# windsensor-esp12-v001.net
KiCad netlist of a schematic drawn in EAGLE
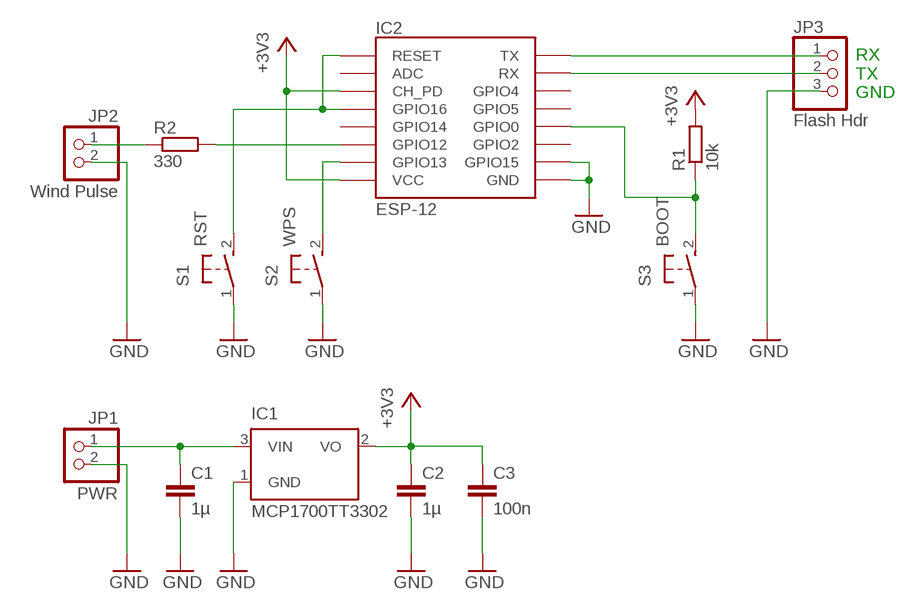
[diagram p0: schematic, sheet 1]

(export (version "E")
  (design (tool "Eeschema 10.0.6"))
  (components
    (comp (ref "C1")
      (value "1µ")
      (footprint "eagle-import:C0805")
      (libsource (lib "eagle-import") (part "C-EUC0805"))
    )
    (comp (ref "C2")
      (value "1µ")
      (footprint "eagle-import:C0805")
      (libsource (lib "eagle-import") (part "C-EUC0805"))
    )
    (comp (ref "C3")
      (value "100n")
      (footprint "eagle-import:C0805")
      (libsource (lib "eagle-import") (part "C-EUC0805"))
    )
    (comp (ref "IC1")
      (value "MCP1700TT3302")
      (footprint "eagle-import:SOT23")
      (libsource (lib "eagle-import") (part "MCP1700TT"))
    )
    (comp (ref "IC2")
      (value "ESP-12")
      (footprint "eagle-import:ESP-12")
      (libsource (lib "eagle-import") (part "ESP-12"))
    )
    (comp (ref "JP1")
      (value "PWR")
      (footprint "eagle-import:1X02")
      (libsource (lib "eagle-import") (part "PINHD-1X2"))
    )
    (comp (ref "JP2")
      (value "Wind Pulse")
      (footprint "eagle-import:1X02")
      (libsource (lib "eagle-import") (part "PINHD-1X2"))
    )
    (comp (ref "JP3")
      (value "Flash Hdr")
      (footprint "eagle-import:1X03")
      (libsource (lib "eagle-import") (part "PINHD-1X3"))
    )
    (comp (ref "R1")
      (value "10k")
      (footprint "eagle-import:R0805HS")
      (libsource (lib "eagle-import") (part "R-EU_R0805HS"))
    )
    (comp (ref "R2")
      (value "330")
      (footprint "eagle-import:R0805HS2")
      (libsource (lib "eagle-import") (part "R-EU_R0805HS2"))
    )
    (comp (ref "S1")
      (value "RST")
      (footprint "eagle-import:TS1")
      (libsource (lib "eagle-import") (part "TS1"))
    )
    (comp (ref "S2")
      (value "WPS")
      (footprint "eagle-import:TS1")
      (libsource (lib "eagle-import") (part "TS1"))
    )
    (comp (ref "S3")
      (value "BOOT")
      (footprint "eagle-import:TS1")
      (libsource (lib "eagle-import") (part "TS1"))
    )
  )
  (nets
    (net (code "1") (name "+3V3") (class "Default")
      (node (ref "C2") (pin "1") (pinfunction "1_1") (pintype "passive"))
      (node (ref "C3") (pin "1") (pinfunction "1_1") (pintype "passive"))
      (node (ref "IC1") (pin "2") (pinfunction "VO_2") (pintype "output"))
      (node (ref "IC2") (pin "CH_PD") (pinfunction "CH_PD_CH_PD") (pintype "bidirectional"))
      (node (ref "IC2") (pin "VCC") (pinfunction "VCC_VCC") (pintype "bidirectional"))
      (node (ref "R1") (pin "2") (pinfunction "2_2") (pintype "passive"))
    )
    (net (code "2") (name "GND") (class "Default")
      (node (ref "C1") (pin "2") (pinfunction "2_2") (pintype "passive"))
      (node (ref "C2") (pin "2") (pinfunction "2_2") (pintype "passive"))
      (node (ref "C3") (pin "2") (pinfunction "2_2") (pintype "passive"))
      (node (ref "IC1") (pin "1") (pinfunction "GND_1") (pintype "passive"))
      (node (ref "IC2") (pin "GND") (pinfunction "GND_GND") (pintype "bidirectional"))
      (node (ref "IC2") (pin "GPIO15") (pinfunction "GPIO15_GPIO15") (pintype "bidirectional"))
      (node (ref "JP1") (pin "2") (pinfunction "2_2") (pintype "passive"))
      (node (ref "JP2") (pin "2") (pinfunction "2_2") (pintype "passive"))
      (node (ref "JP3") (pin "3") (pinfunction "3_3") (pintype "passive"))
      (node (ref "S1") (pin "1") (pinfunction "1_1") (pintype "passive"))
      (node (ref "S2") (pin "1") (pinfunction "1_1") (pintype "passive"))
      (node (ref "S3") (pin "1") (pinfunction "1_1") (pintype "passive"))
    )
    (net (code "3") (name "Net-(IC1-VIN)") (class "Default")
      (node (ref "C1") (pin "1") (pinfunction "1_1") (pintype "passive"))
      (node (ref "IC1") (pin "3") (pinfunction "VIN_3") (pintype "input"))
      (node (ref "JP1") (pin "1") (pinfunction "1_1") (pintype "passive"))
    )
    (net (code "4") (name "Net-(IC2-PadGPIO0)") (class "Default")
      (node (ref "IC2") (pin "GPIO0") (pinfunction "GPIO0_GPIO0") (pintype "bidirectional"))
      (node (ref "R1") (pin "1") (pinfunction "1_1") (pintype "passive"))
      (node (ref "S3") (pin "2") (pinfunction "2_2") (pintype "passive"))
    )
    (net (code "5") (name "Net-(IC2-PadGPIO12)") (class "Default")
      (node (ref "IC2") (pin "GPIO12") (pinfunction "GPIO12_GPIO12") (pintype "bidirectional"))
      (node (ref "R2") (pin "2") (pinfunction "2_2") (pintype "passive"))
    )
    (net (code "6") (name "Net-(IC2-PadGPIO13)") (class "Default")
      (node (ref "IC2") (pin "GPIO13") (pinfunction "GPIO13_GPIO13") (pintype "bidirectional"))
      (node (ref "S2") (pin "2") (pinfunction "2_2") (pintype "passive"))
    )
    (net (code "7") (name "Net-(IC2-PadGPIO16)") (class "Default")
      (node (ref "IC2") (pin "GPIO16") (pinfunction "GPIO16_GPIO16") (pintype "bidirectional"))
      (node (ref "IC2") (pin "RESET") (pinfunction "RESET_RESET") (pintype "bidirectional"))
      (node (ref "S1") (pin "2") (pinfunction "2_2") (pintype "passive"))
    )
    (net (code "8") (name "Net-(IC2-PadRX)") (class "Default")
      (node (ref "IC2") (pin "RX") (pinfunction "RX_RX") (pintype "bidirectional"))
      (node (ref "JP3") (pin "2") (pinfunction "2_2") (pintype "passive"))
    )
    (net (code "9") (name "Net-(IC2-PadTX)") (class "Default")
      (node (ref "IC2") (pin "TX") (pinfunction "TX_TX") (pintype "bidirectional"))
      (node (ref "JP3") (pin "1") (pinfunction "1_1") (pintype "passive"))
    )
    (net (code "10") (name "Net-(JP2-Pad1)") (class "Default")
      (node (ref "JP2") (pin "1") (pinfunction "1_1") (pintype "passive"))
      (node (ref "R2") (pin "1") (pinfunction "1_1") (pintype "passive"))
    )
    (net (code "11") (name "unconnected-(IC2-PadADC)") (class "Default")
      (node (ref "IC2") (pin "ADC") (pinfunction "ADC_ADC") (pintype "bidirectional"))
    )
    (net (code "12") (name "unconnected-(IC2-PadGPIO2)") (class "Default")
      (node (ref "IC2") (pin "GPIO2") (pinfunction "GPIO2_GPIO2") (pintype "bidirectional"))
    )
    (net (code "13") (name "unconnected-(IC2-PadGPIO4)") (class "Default")
      (node (ref "IC2") (pin "GPIO4") (pinfunction "GPIO4_GPIO4") (pintype "bidirectional"))
    )
    (net (code "14") (name "unconnected-(IC2-PadGPIO5)") (class "Default")
      (node (ref "IC2") (pin "GPIO5") (pinfunction "GPIO5_GPIO5") (pintype "bidirectional"))
    )
    (net (code "15") (name "unconnected-(IC2-PadGPIO14)") (class "Default")
      (node (ref "IC2") (pin "GPIO14") (pinfunction "GPIO14_GPIO14") (pintype "bidirectional"))
    )
  )
)
